# timelapse.net
KiCad netlist of a schematic drawn in EAGLE
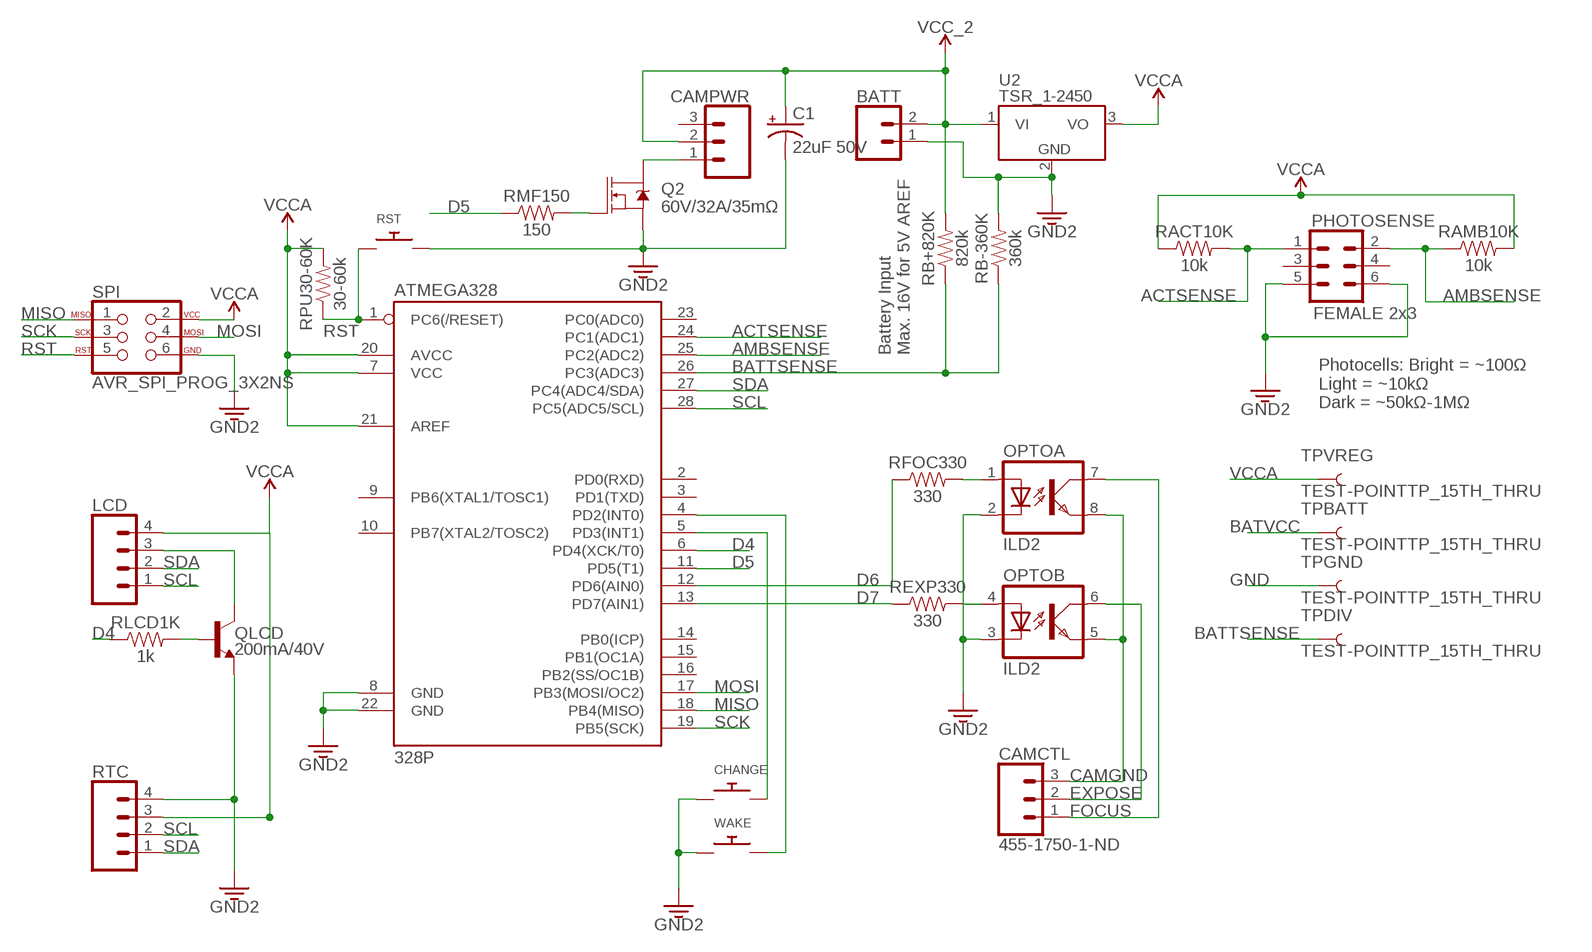
[diagram p0: schematic, sheet 1]

(export (version "E")
  (design (tool "Eeschema 10.0.6"))
  (components
    (comp (ref "ATMEGA328")
      (value "328P")
      (footprint "eagle-import:DIP28")
      (libsource (lib "eagle-import") (part "ATMEGA328P_PDIP"))
    )
    (comp (ref "BATT")
      (value "CONN_02")
      (footprint "eagle-import:1X02")
      (libsource (lib "eagle-import") (part "CONN_02"))
    )
    (comp (ref "C1")
      (value "22uF 50V")
      (footprint "eagle-import:CPOL-RADIAL-2.5MM-5MM")
      (libsource (lib "eagle-import") (part "10UF-POLAR-RADIAL-2.5MM-25V-20%"))
    )
    (comp (ref "CAMCTL")
      (value "455-1750-1-ND")
      (footprint "eagle-import:1X03")
      (libsource (lib "eagle-import") (part "CONN_03"))
    )
    (comp (ref "CAMPWR")
      (value "CONN_03")
      (footprint "eagle-import:1X03")
      (libsource (lib "eagle-import") (part "CONN_03"))
    )
    (comp (ref "CHANGE")
      (value "SWITCH_PUSHBUTTONEVQ-PE")
      (footprint "eagle-import:TACT_PANA-EVQ")
      (libsource (lib "eagle-import") (part "SWITCH_PUSHBUTTONEVQ-PE"))
    )
    (comp (ref "LCD")
      (value "CONN_04")
      (footprint "eagle-import:1X04")
      (libsource (lib "eagle-import") (part "CONN_04"))
    )
    (comp (ref "OPTO")
      (value "ILD2")
      (footprint "eagle-import:DIL08")
      (libsource (lib "eagle-import") (part "ILD2"))
    )
    (comp (ref "PHOTOSENSE")
      (value "FEMALE 2x3")
      (footprint "eagle-import:2X3")
      (libsource (lib "eagle-import") (part "CONN_03X2FEMALE"))
    )
    (comp (ref "Q2")
      (value "60V/32A/35mΩ")
      (footprint "eagle-import:TO220V")
      (libsource (lib "eagle-import") (part "MOSFET-NCH-FQP30N06L"))
    )
    (comp (ref "QLCD")
      (value "200mA/40V")
      (footprint "eagle-import:TO-92")
      (libsource (lib "eagle-import") (part "TRANS_NPN-2N3904"))
    )
    (comp (ref "RACT10K")
      (value "10k")
      (footprint "eagle-import:AXIAL-0.3")
      (libsource (lib "eagle-import") (part "10KOHM-HORIZ-1/4W-1%"))
    )
    (comp (ref "RAMB10K")
      (value "10k")
      (footprint "eagle-import:AXIAL-0.3")
      (libsource (lib "eagle-import") (part "10KOHM-HORIZ-1/4W-1%"))
    )
    (comp (ref "RB+820K")
      (value "820k")
      (footprint "eagle-import:AXIAL-0.3")
      (libsource (lib "eagle-import") (part "10KOHM-HORIZ-1/4W-1%"))
    )
    (comp (ref "RB-360K")
      (value "360k")
      (footprint "eagle-import:AXIAL-0.3")
      (libsource (lib "eagle-import") (part "10KOHM-HORIZ-1/4W-1%"))
    )
    (comp (ref "REXP330")
      (value "330")
      (footprint "eagle-import:AXIAL-0.3")
      (libsource (lib "eagle-import") (part "330OHM-HORIZ-1/10W-5%"))
    )
    (comp (ref "RFOC330")
      (value "330")
      (footprint "eagle-import:AXIAL-0.3")
      (libsource (lib "eagle-import") (part "330OHM-HORIZ-1/10W-5%"))
    )
    (comp (ref "RLCD1K")
      (value "1k")
      (footprint "eagle-import:AXIAL-0.3")
      (libsource (lib "eagle-import") (part "330OHM-HORIZ-1/10W-5%"))
    )
    (comp (ref "RMF150")
      (value "150")
      (footprint "eagle-import:AXIAL-0.3")
      (libsource (lib "eagle-import") (part "330OHM-HORIZ-1/10W-5%"))
    )
    (comp (ref "RPU30-60K")
      (value "30-60k")
      (footprint "eagle-import:AXIAL-0.3")
      (libsource (lib "eagle-import") (part "330OHM-HORIZ-1/10W-5%"))
    )
    (comp (ref "RST")
      (value "SWITCH_PUSHBUTTONEVQ-PE")
      (footprint "eagle-import:TACT_PANA-EVQ")
      (libsource (lib "eagle-import") (part "SWITCH_PUSHBUTTONEVQ-PE"))
    )
    (comp (ref "RTC")
      (value "CONN_04")
      (footprint "eagle-import:1X04")
      (libsource (lib "eagle-import") (part "CONN_04"))
    )
    (comp (ref "SPI")
      (value "AVR_SPI_PROG_3X2NS")
      (footprint "eagle-import:2X3-NS")
      (libsource (lib "eagle-import") (part "AVR_SPI_PROG_3X2NS"))
    )
    (comp (ref "TPBATT")
      (value "TEST-POINTTP_15TH_THRU")
      (footprint "eagle-import:TP_15TH")
      (libsource (lib "eagle-import") (part "TEST-POINTTP_15TH_THRU"))
    )
    (comp (ref "TPDIV")
      (value "TEST-POINTTP_15TH_THRU")
      (footprint "eagle-import:TP_15TH")
      (libsource (lib "eagle-import") (part "TEST-POINTTP_15TH_THRU"))
    )
    (comp (ref "TPGND")
      (value "TEST-POINTTP_15TH_THRU")
      (footprint "eagle-import:TP_15TH")
      (libsource (lib "eagle-import") (part "TEST-POINTTP_15TH_THRU"))
    )
    (comp (ref "TPVREG")
      (value "TEST-POINTTP_15TH_THRU")
      (footprint "eagle-import:TP_15TH")
      (libsource (lib "eagle-import") (part "TEST-POINTTP_15TH_THRU"))
    )
    (comp (ref "U2")
      (value "TSR_1-2450")
      (footprint "eagle-import:TSR-1")
      (libsource (lib "eagle-import") (part "TSR_1-2450"))
    )
    (comp (ref "WAKE")
      (value "SWITCH_PUSHBUTTONEVQ-PE")
      (footprint "eagle-import:TACT_PANA-EVQ")
      (libsource (lib "eagle-import") (part "SWITCH_PUSHBUTTONEVQ-PE"))
    )
  )
  (nets
    (net (code "1") (name "/ACTSENSE") (class "Default")
      (node (ref "ATMEGA328") (pin "24") (pinfunction "PC1(ADC1)_24") (pintype "bidirectional"))
      (node (ref "PHOTOSENSE") (pin "1") (pinfunction "1_1") (pintype "bidirectional"))
      (node (ref "RACT10K") (pin "P$2") (pinfunction "2_P$2") (pintype "passive"))
    )
    (net (code "2") (name "/AMBSENSE") (class "Default")
      (node (ref "ATMEGA328") (pin "25") (pinfunction "PC2(ADC2)_25") (pintype "bidirectional"))
      (node (ref "PHOTOSENSE") (pin "2") (pinfunction "2_2") (pintype "bidirectional"))
      (node (ref "RAMB10K") (pin "P$1") (pinfunction "1_P$1") (pintype "passive"))
    )
    (net (code "3") (name "/BATTSENSE") (class "Default")
      (node (ref "ATMEGA328") (pin "26") (pinfunction "PC3(ADC3)_26") (pintype "bidirectional"))
      (node (ref "RB+820K") (pin "P$1") (pinfunction "1_P$1") (pintype "passive"))
      (node (ref "RB-360K") (pin "P$1") (pinfunction "1_P$1") (pintype "passive"))
      (node (ref "TPDIV") (pin "P$1") (pinfunction "1_P$1") (pintype "bidirectional"))
    )
    (net (code "4") (name "/CAMGND") (class "Default")
      (node (ref "CAMCTL") (pin "3") (pinfunction "3_3") (pintype "passive"))
      (node (ref "OPTO") (pin "5") (pinfunction "EMIT_5") (pintype "passive"))
      (node (ref "OPTO") (pin "8") (pinfunction "EMIT_8") (pintype "passive"))
    )
    (net (code "5") (name "/D4") (class "Default")
      (node (ref "ATMEGA328") (pin "6") (pinfunction "PD4(XCK/T0)_6") (pintype "bidirectional"))
      (node (ref "RLCD1K") (pin "P$1") (pinfunction "1_P$1") (pintype "passive"))
    )
    (net (code "6") (name "/D5") (class "Default")
      (node (ref "ATMEGA328") (pin "11") (pinfunction "PD5(T1)_11") (pintype "bidirectional"))
      (node (ref "RMF150") (pin "P$1") (pinfunction "1_P$1") (pintype "passive"))
    )
    (net (code "7") (name "/D6") (class "Default")
      (node (ref "ATMEGA328") (pin "12") (pinfunction "PD6(AIN0)_12") (pintype "bidirectional"))
      (node (ref "RFOC330") (pin "P$1") (pinfunction "1_P$1") (pintype "passive"))
    )
    (net (code "8") (name "/D7") (class "Default")
      (node (ref "ATMEGA328") (pin "13") (pinfunction "PD7(AIN1)_13") (pintype "bidirectional"))
      (node (ref "REXP330") (pin "P$1") (pinfunction "1_P$1") (pintype "passive"))
    )
    (net (code "9") (name "/EXPOSE") (class "Default")
      (node (ref "CAMCTL") (pin "2") (pinfunction "2_2") (pintype "passive"))
      (node (ref "OPTO") (pin "6") (pinfunction "COL_6") (pintype "passive"))
    )
    (net (code "10") (name "/FOCUS") (class "Default")
      (node (ref "CAMCTL") (pin "1") (pinfunction "1_1") (pintype "passive"))
      (node (ref "OPTO") (pin "7") (pinfunction "COL_7") (pintype "passive"))
    )
    (net (code "11") (name "/MISO") (class "Default")
      (node (ref "ATMEGA328") (pin "18") (pinfunction "PB4(MISO)_18") (pintype "bidirectional"))
      (node (ref "SPI") (pin "1") (pinfunction "1_1") (pintype "passive"))
    )
    (net (code "12") (name "/MOSI") (class "Default")
      (node (ref "ATMEGA328") (pin "17") (pinfunction "PB3(MOSI/OC2)_17") (pintype "bidirectional"))
      (node (ref "SPI") (pin "4") (pinfunction "4_4") (pintype "passive"))
    )
    (net (code "13") (name "/RST") (class "Default")
      (node (ref "ATMEGA328") (pin "1") (pinfunction "PC6(/RESET)_1") (pintype "bidirectional"))
      (node (ref "RPU30-60K") (pin "P$1") (pinfunction "1_P$1") (pintype "passive"))
      (node (ref "RST") (pin "P$1") (pinfunction "P$1_P$1") (pintype "passive"))
      (node (ref "SPI") (pin "5") (pinfunction "5_5") (pintype "passive"))
    )
    (net (code "14") (name "/SCK") (class "Default")
      (node (ref "ATMEGA328") (pin "19") (pinfunction "PB5(SCK)_19") (pintype "bidirectional"))
      (node (ref "SPI") (pin "3") (pinfunction "3_3") (pintype "passive"))
    )
    (net (code "15") (name "/SCL") (class "Default")
      (node (ref "ATMEGA328") (pin "28") (pinfunction "PC5(ADC5/SCL)_28") (pintype "bidirectional"))
      (node (ref "LCD") (pin "1") (pinfunction "1_1") (pintype "passive"))
      (node (ref "RTC") (pin "2") (pinfunction "2_2") (pintype "passive"))
    )
    (net (code "16") (name "/SDA") (class "Default")
      (node (ref "ATMEGA328") (pin "27") (pinfunction "PC4(ADC4/SDA)_27") (pintype "bidirectional"))
      (node (ref "LCD") (pin "2") (pinfunction "2_2") (pintype "passive"))
      (node (ref "RTC") (pin "1") (pinfunction "1_1") (pintype "passive"))
    )
    (net (code "17") (name "GND2") (class "Default")
      (node (ref "ATMEGA328") (pin "22") (pinfunction "GND_22") (pintype "bidirectional"))
      (node (ref "ATMEGA328") (pin "8") (pinfunction "GND_8") (pintype "bidirectional"))
      (node (ref "BATT") (pin "1") (pinfunction "1_1") (pintype "passive"))
      (node (ref "C1") (pin "2") (pinfunction "-_2") (pintype "passive"))
      (node (ref "CHANGE") (pin "P$1") (pinfunction "P$1_P$1") (pintype "passive"))
      (node (ref "OPTO") (pin "2") (pinfunction "C_2") (pintype "passive"))
      (node (ref "OPTO") (pin "3") (pinfunction "C_3") (pintype "passive"))
      (node (ref "PHOTOSENSE") (pin "5") (pinfunction "5_5") (pintype "bidirectional"))
      (node (ref "PHOTOSENSE") (pin "6") (pinfunction "6_6") (pintype "bidirectional"))
      (node (ref "Q2") (pin "3") (pinfunction "S_3") (pintype "bidirectional"))
      (node (ref "QLCD") (pin "1") (pinfunction "E_1") (pintype "passive"))
      (node (ref "RB-360K") (pin "P$2") (pinfunction "2_P$2") (pintype "passive"))
      (node (ref "RST") (pin "P$2") (pinfunction "P$2_P$2") (pintype "passive"))
      (node (ref "RTC") (pin "4") (pinfunction "4_4") (pintype "passive"))
      (node (ref "SPI") (pin "6") (pinfunction "6_6") (pintype "passive"))
      (node (ref "TPGND") (pin "P$1") (pinfunction "1_P$1") (pintype "bidirectional"))
      (node (ref "U2") (pin "2") (pinfunction "GND_2") (pintype "power_in"))
      (node (ref "WAKE") (pin "P$1") (pinfunction "P$1_P$1") (pintype "passive"))
    )
    (net (code "18") (name "Net-(ATMEGA328-PD2(INT0))") (class "Default")
      (node (ref "ATMEGA328") (pin "4") (pinfunction "PD2(INT0)_4") (pintype "bidirectional"))
      (node (ref "WAKE") (pin "P$2") (pinfunction "P$2_P$2") (pintype "passive"))
    )
    (net (code "19") (name "Net-(ATMEGA328-PD3(INT1))") (class "Default")
      (node (ref "ATMEGA328") (pin "5") (pinfunction "PD3(INT1)_5") (pintype "bidirectional"))
      (node (ref "CHANGE") (pin "P$2") (pinfunction "P$2_P$2") (pintype "passive"))
    )
    (net (code "20") (name "Net-(OPTOA-A)") (class "Default")
      (node (ref "OPTO") (pin "1") (pinfunction "A_1") (pintype "passive"))
      (node (ref "RFOC330") (pin "P$2") (pinfunction "2_P$2") (pintype "passive"))
    )
    (net (code "21") (name "Net-(OPTOB-A)") (class "Default")
      (node (ref "OPTO") (pin "4") (pinfunction "A_4") (pintype "passive"))
      (node (ref "REXP330") (pin "P$2") (pinfunction "2_P$2") (pintype "passive"))
    )
    (net (code "22") (name "Net-(Q2-D)") (class "Default")
      (node (ref "CAMPWR") (pin "1") (pinfunction "1_1") (pintype "passive"))
      (node (ref "Q2") (pin "2") (pinfunction "D_2") (pintype "bidirectional"))
    )
    (net (code "23") (name "Net-(Q2-G)") (class "Default")
      (node (ref "Q2") (pin "1") (pinfunction "G_1") (pintype "bidirectional"))
      (node (ref "RMF150") (pin "P$2") (pinfunction "2_P$2") (pintype "passive"))
    )
    (net (code "24") (name "Net-(QLCD-B)") (class "Default")
      (node (ref "QLCD") (pin "2") (pinfunction "B_2") (pintype "passive"))
      (node (ref "RLCD1K") (pin "P$2") (pinfunction "2_P$2") (pintype "passive"))
    )
    (net (code "25") (name "Net-(QLCD-C)") (class "Default")
      (node (ref "LCD") (pin "3") (pinfunction "3_3") (pintype "passive"))
      (node (ref "QLCD") (pin "3") (pinfunction "C_3") (pintype "passive"))
    )
    (net (code "26") (name "VCCA") (class "Default")
      (node (ref "ATMEGA328") (pin "20") (pinfunction "AVCC_20") (pintype "bidirectional"))
      (node (ref "ATMEGA328") (pin "21") (pinfunction "AREF_21") (pintype "bidirectional"))
      (node (ref "ATMEGA328") (pin "7") (pinfunction "VCC_7") (pintype "bidirectional"))
      (node (ref "LCD") (pin "4") (pinfunction "4_4") (pintype "passive"))
      (node (ref "RACT10K") (pin "P$1") (pinfunction "1_P$1") (pintype "passive"))
      (node (ref "RAMB10K") (pin "P$2") (pinfunction "2_P$2") (pintype "passive"))
      (node (ref "RPU30-60K") (pin "P$2") (pinfunction "2_P$2") (pintype "passive"))
      (node (ref "RTC") (pin "3") (pinfunction "3_3") (pintype "passive"))
      (node (ref "SPI") (pin "2") (pinfunction "2_2") (pintype "passive"))
      (node (ref "TPVREG") (pin "P$1") (pinfunction "1_P$1") (pintype "bidirectional"))
      (node (ref "U2") (pin "3") (pinfunction "VO_3") (pintype "power_in"))
    )
    (net (code "27") (name "VCC_2") (class "Default")
      (node (ref "BATT") (pin "2") (pinfunction "2_2") (pintype "passive"))
      (node (ref "C1") (pin "1") (pinfunction "+_1") (pintype "passive"))
      (node (ref "CAMPWR") (pin "2") (pinfunction "2_2") (pintype "passive"))
      (node (ref "RB+820K") (pin "P$2") (pinfunction "2_P$2") (pintype "passive"))
      (node (ref "TPBATT") (pin "P$1") (pinfunction "1_P$1") (pintype "bidirectional"))
      (node (ref "U2") (pin "1") (pinfunction "VI_1") (pintype "power_in"))
    )
    (net (code "28") (name "unconnected-(ATMEGA328-PB0(ICP)-Pad14)") (class "Default")
      (node (ref "ATMEGA328") (pin "14") (pinfunction "PB0(ICP)_14") (pintype "bidirectional"))
    )
    (net (code "29") (name "unconnected-(ATMEGA328-PB1(OC1A)-Pad15)") (class "Default")
      (node (ref "ATMEGA328") (pin "15") (pinfunction "PB1(OC1A)_15") (pintype "bidirectional"))
    )
    (net (code "30") (name "unconnected-(ATMEGA328-PB2(SS{slash}OC1B)-Pad16)") (class "Default")
      (node (ref "ATMEGA328") (pin "16") (pinfunction "PB2(SS/OC1B)_16") (pintype "bidirectional"))
    )
    (net (code "31") (name "unconnected-(ATMEGA328-PB6(XTAL1{slash}TOSC1)-Pad9)") (class "Default")
      (node (ref "ATMEGA328") (pin "9") (pinfunction "PB6(XTAL1/TOSC1)_9") (pintype "bidirectional"))
    )
    (net (code "32") (name "unconnected-(ATMEGA328-PB7(XTAL2{slash}TOSC2)-Pad10)") (class "Default")
      (node (ref "ATMEGA328") (pin "10") (pinfunction "PB7(XTAL2/TOSC2)_10") (pintype "bidirectional"))
    )
    (net (code "33") (name "unconnected-(ATMEGA328-PC0(ADC0)-Pad23)") (class "Default")
      (node (ref "ATMEGA328") (pin "23") (pinfunction "PC0(ADC0)_23") (pintype "bidirectional"))
    )
    (net (code "34") (name "unconnected-(ATMEGA328-PD0(RXD)-Pad2)") (class "Default")
      (node (ref "ATMEGA328") (pin "2") (pinfunction "PD0(RXD)_2") (pintype "bidirectional"))
    )
    (net (code "35") (name "unconnected-(ATMEGA328-PD1(TXD)-Pad3)") (class "Default")
      (node (ref "ATMEGA328") (pin "3") (pinfunction "PD1(TXD)_3") (pintype "bidirectional"))
    )
    (net (code "36") (name "unconnected-(CAMPWR-Pad3)") (class "Default")
      (node (ref "CAMPWR") (pin "3") (pinfunction "3_3") (pintype "passive"))
    )
    (net (code "37") (name "unconnected-(PHOTOSENSE-Pad3)") (class "Default")
      (node (ref "PHOTOSENSE") (pin "3") (pinfunction "3_3") (pintype "bidirectional"))
    )
    (net (code "38") (name "unconnected-(PHOTOSENSE-Pad4)") (class "Default")
      (node (ref "PHOTOSENSE") (pin "4") (pinfunction "4_4") (pintype "bidirectional"))
    )
  )
)
